# 14SD.net
KiCad netlist of a schematic drawn in Altium Designer
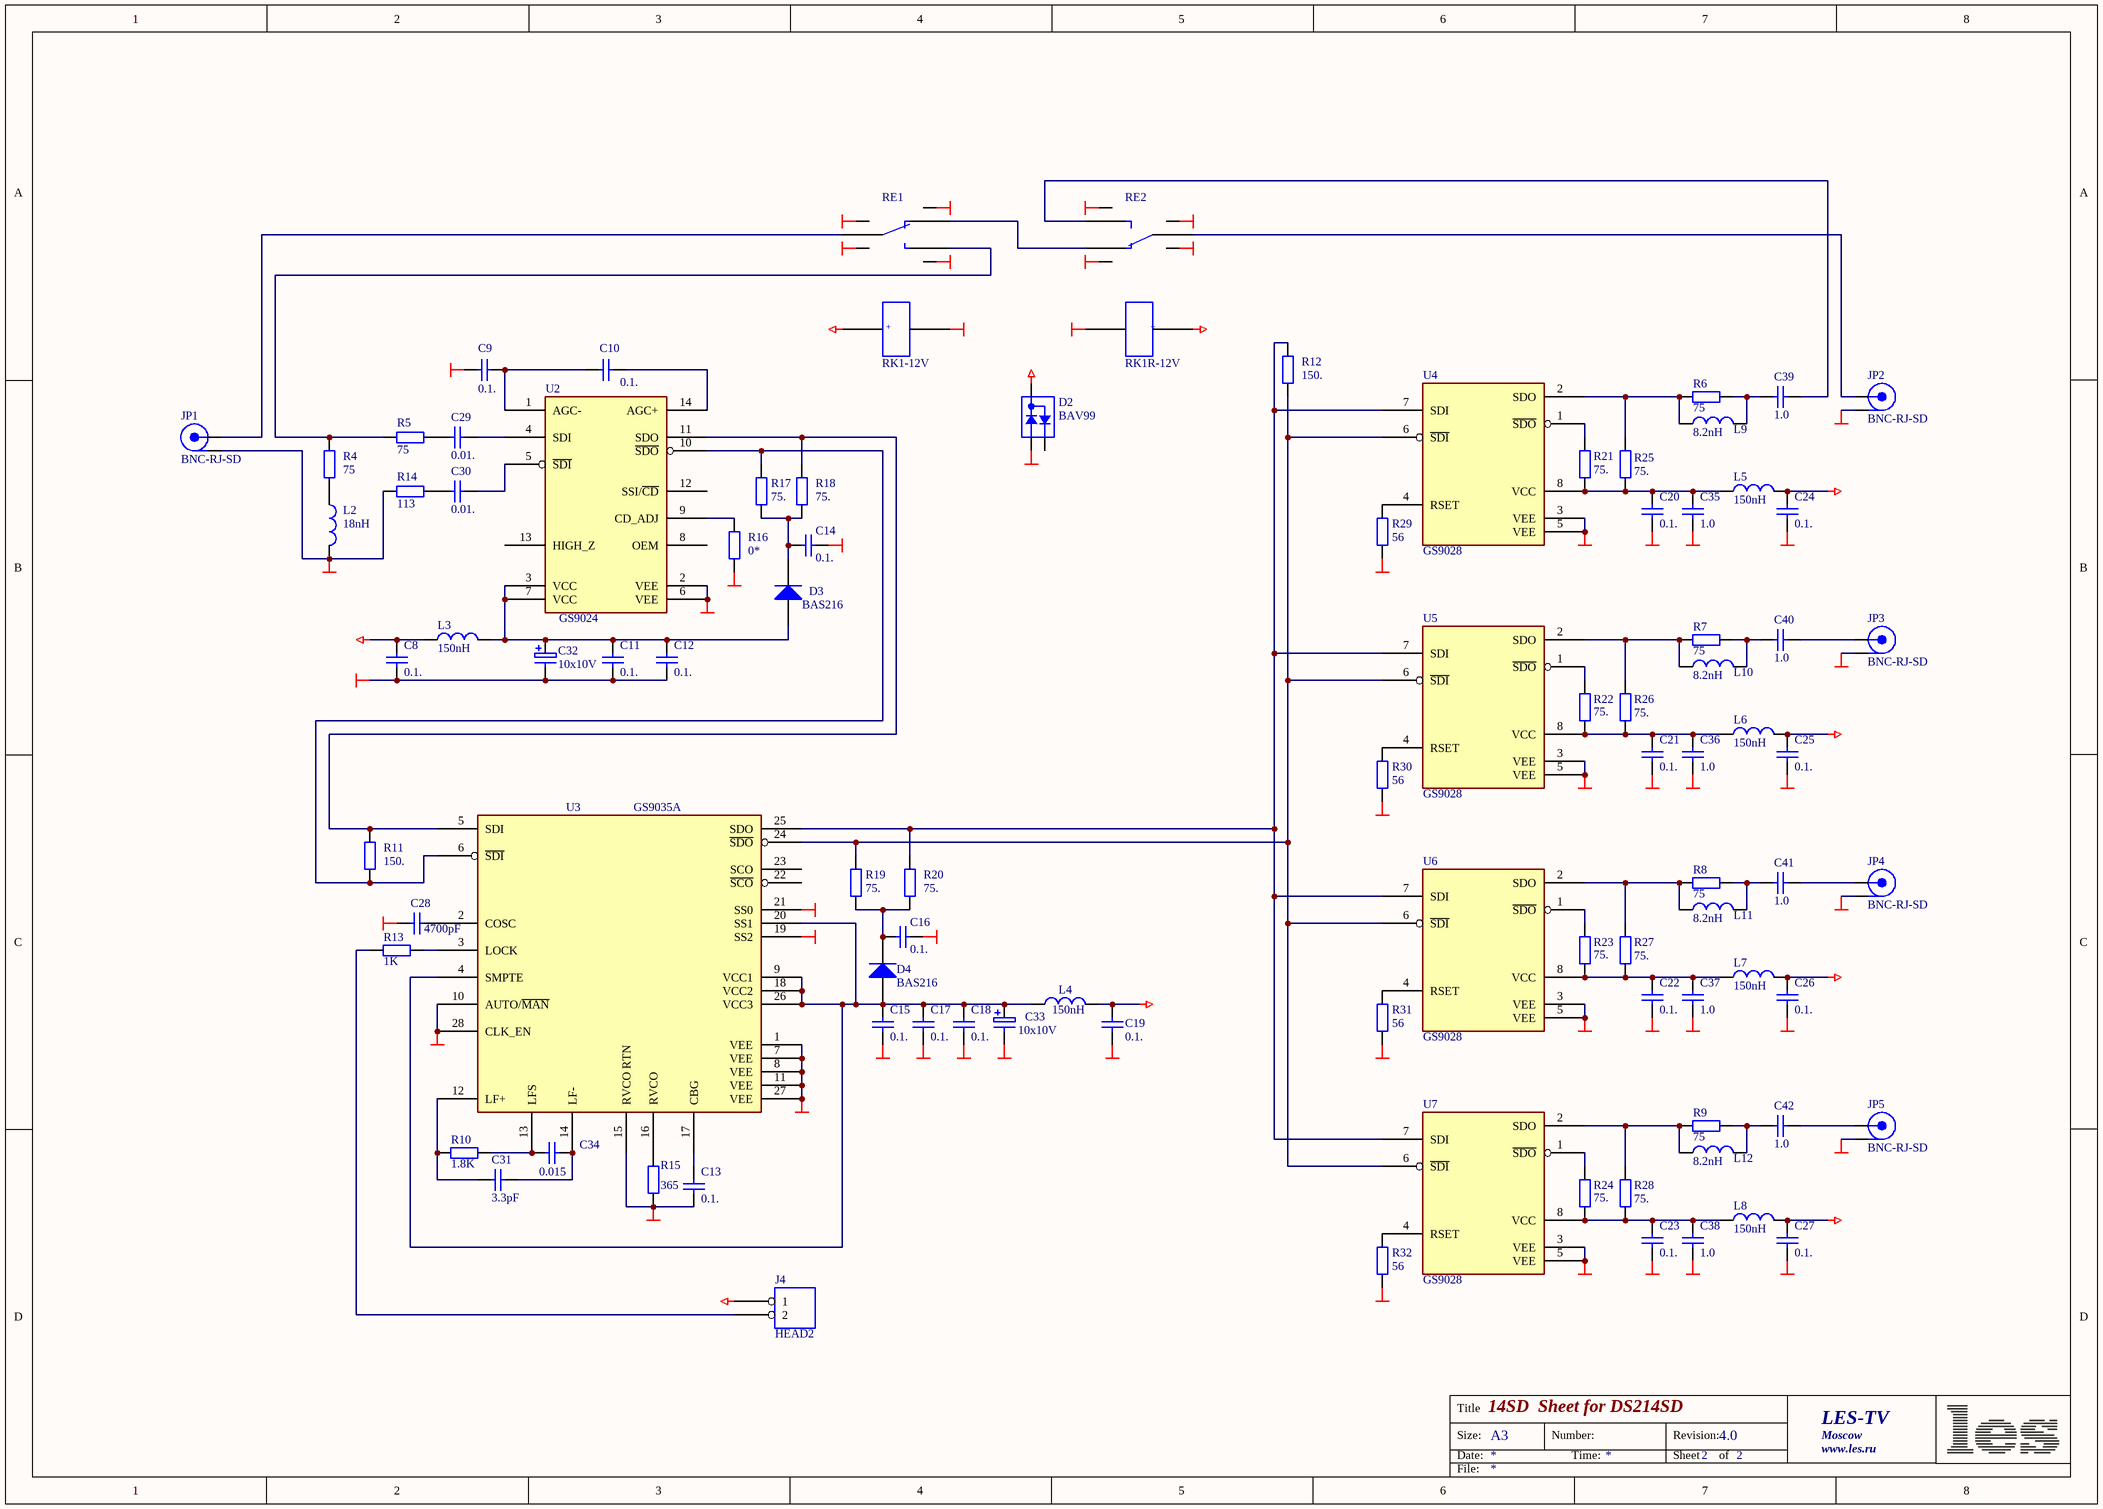
[diagram p0: 14SD.SchDoc]

(export (version "E")
  (design (tool "Eeschema 10.0.6"))
  (components
    (comp (ref "C8")
      (value "0.1.")
      (footprint "C0402")
      (description "Capacitor")
      (fields (field (name "MANUFACTURER") "Generic Components") (field (name "PUBLISHER") "Altium Limited"))
      (libsource (lib "LES") (part "Cap"))
    )
    (comp (ref "C9")
      (value "0.1.")
      (footprint "C0402")
      (description "Capacitor")
      (fields (field (name "MANUFACTURER") "Generic Components") (field (name "PUBLISHER") "Altium Limited"))
      (libsource (lib "LES") (part "Cap"))
    )
    (comp (ref "C10")
      (value "0.1.")
      (footprint "C0402")
      (description "Capacitor")
      (fields (field (name "MANUFACTURER") "Generic Components") (field (name "PUBLISHER") "Altium Limited"))
      (libsource (lib "LES") (part "Cap"))
    )
    (comp (ref "C11")
      (value "0.1.")
      (footprint "C0402")
      (description "Capacitor")
      (fields (field (name "MANUFACTURER") "Generic Components") (field (name "PUBLISHER") "Altium Limited"))
      (libsource (lib "LES") (part "Cap"))
    )
    (comp (ref "C12")
      (value "0.1.")
      (footprint "C0402")
      (description "Capacitor")
      (fields (field (name "MANUFACTURER") "Generic Components") (field (name "PUBLISHER") "Altium Limited"))
      (libsource (lib "LES") (part "Cap"))
    )
    (comp (ref "C13")
      (value "0.1.")
      (footprint "C0402")
      (description "Capacitor")
      (fields (field (name "MANUFACTURER") "Generic Components") (field (name "PUBLISHER") "Altium Limited"))
      (libsource (lib "LES") (part "Cap"))
    )
    (comp (ref "C14")
      (value "0.1.")
      (footprint "C0402")
      (description "Capacitor")
      (fields (field (name "MANUFACTURER") "Generic Components") (field (name "PUBLISHER") "Altium Limited"))
      (libsource (lib "LES") (part "Cap"))
    )
    (comp (ref "C15")
      (value "0.1.")
      (footprint "C0402")
      (description "Capacitor")
      (fields (field (name "MANUFACTURER") "Generic Components") (field (name "PUBLISHER") "Altium Limited"))
      (libsource (lib "LES") (part "Cap"))
    )
    (comp (ref "C16")
      (value "0.1.")
      (footprint "C0402")
      (description "Capacitor")
      (fields (field (name "MANUFACTURER") "Generic Components") (field (name "PUBLISHER") "Altium Limited"))
      (libsource (lib "LES") (part "Cap"))
    )
    (comp (ref "C17")
      (value "0.1.")
      (footprint "C0402")
      (description "Capacitor")
      (fields (field (name "MANUFACTURER") "Generic Components") (field (name "PUBLISHER") "Altium Limited"))
      (libsource (lib "LES") (part "Cap"))
    )
    (comp (ref "C18")
      (value "0.1.")
      (footprint "C0402")
      (description "Capacitor")
      (fields (field (name "MANUFACTURER") "Generic Components") (field (name "PUBLISHER") "Altium Limited"))
      (libsource (lib "LES") (part "Cap"))
    )
    (comp (ref "C19")
      (value "0.1.")
      (footprint "C0402")
      (description "Capacitor")
      (fields (field (name "MANUFACTURER") "Generic Components") (field (name "PUBLISHER") "Altium Limited"))
      (libsource (lib "LES") (part "Cap"))
    )
    (comp (ref "C20")
      (value "0.1.")
      (footprint "C0402")
      (description "Capacitor")
      (fields (field (name "MANUFACTURER") "Generic Components") (field (name "PUBLISHER") "Altium Limited"))
      (libsource (lib "LES") (part "Cap"))
    )
    (comp (ref "C21")
      (value "0.1.")
      (footprint "C0402")
      (description "Capacitor")
      (fields (field (name "MANUFACTURER") "Generic Components") (field (name "PUBLISHER") "Altium Limited"))
      (libsource (lib "LES") (part "Cap"))
    )
    (comp (ref "C22")
      (value "0.1.")
      (footprint "C0402")
      (description "Capacitor")
      (fields (field (name "MANUFACTURER") "Generic Components") (field (name "PUBLISHER") "Altium Limited"))
      (libsource (lib "LES") (part "Cap"))
    )
    (comp (ref "C23")
      (value "0.1.")
      (footprint "C0402")
      (description "Capacitor")
      (fields (field (name "MANUFACTURER") "Generic Components") (field (name "PUBLISHER") "Altium Limited"))
      (libsource (lib "LES") (part "Cap"))
    )
    (comp (ref "C24")
      (value "0.1.")
      (footprint "C0402")
      (description "Capacitor")
      (fields (field (name "MANUFACTURER") "Generic Components") (field (name "PUBLISHER") "Altium Limited"))
      (libsource (lib "LES") (part "Cap"))
    )
    (comp (ref "C25")
      (value "0.1.")
      (footprint "C0402")
      (description "Capacitor")
      (fields (field (name "MANUFACTURER") "Generic Components") (field (name "PUBLISHER") "Altium Limited"))
      (libsource (lib "LES") (part "Cap"))
    )
    (comp (ref "C26")
      (value "0.1.")
      (footprint "C0402")
      (description "Capacitor")
      (fields (field (name "MANUFACTURER") "Generic Components") (field (name "PUBLISHER") "Altium Limited"))
      (libsource (lib "LES") (part "Cap"))
    )
    (comp (ref "C27")
      (value "0.1.")
      (footprint "C0402")
      (description "Capacitor")
      (fields (field (name "MANUFACTURER") "Generic Components") (field (name "PUBLISHER") "Altium Limited"))
      (libsource (lib "LES") (part "Cap"))
    )
    (comp (ref "C28")
      (value "4700pF")
      (footprint "C0805")
      (description "Capacitor")
      (fields (field (name "MANUFACTURER") "Generic Components") (field (name "PUBLISHER") "Altium Limited"))
      (libsource (lib "LES") (part "Cap"))
    )
    (comp (ref "C29")
      (value "0.01.")
      (footprint "C0402")
      (description "Capacitor")
      (fields (field (name "MANUFACTURER") "Generic Components") (field (name "PUBLISHER") "Altium Limited"))
      (libsource (lib "LES") (part "Cap"))
    )
    (comp (ref "C30")
      (value "0.01.")
      (footprint "C0402")
      (description "Capacitor")
      (fields (field (name "MANUFACTURER") "Generic Components") (field (name "PUBLISHER") "Altium Limited"))
      (libsource (lib "LES") (part "Cap"))
    )
    (comp (ref "C31")
      (value "3.3pF")
      (footprint "C0805")
      (description "Capacitor")
      (fields (field (name "MANUFACTURER") "Generic Components") (field (name "PUBLISHER") "Altium Limited"))
      (libsource (lib "LES") (part "Cap"))
    )
    (comp (ref "C32")
      (value "10x10V")
      (footprint "TA1206")
      (description "Polarized Capacitor (Radial)")
      (fields (field (name "MANUFACTURER") "Generic Components") (field (name "PUBLISHER") "Altium Limited"))
      (libsource (lib "LES") (part "Cap Pol"))
    )
    (comp (ref "C33")
      (value "10x10V")
      (footprint "TA1206")
      (description "Polarized Capacitor (Radial)")
      (fields (field (name "MANUFACTURER") "Generic Components") (field (name "PUBLISHER") "Altium Limited"))
      (libsource (lib "LES") (part "Cap Pol"))
    )
    (comp (ref "C34")
      (value "0.015")
      (footprint "C0805")
      (description "Capacitor")
      (fields (field (name "MANUFACTURER") "Generic Components") (field (name "PUBLISHER") "Altium Limited"))
      (libsource (lib "LES") (part "Cap"))
    )
    (comp (ref "C35")
      (value "1.0")
      (footprint "C0805")
      (description "Capacitor")
      (fields (field (name "MANUFACTURER") "Generic Components") (field (name "PUBLISHER") "Altium Limited"))
      (libsource (lib "LES") (part "Cap"))
    )
    (comp (ref "C36")
      (value "1.0")
      (footprint "C0805")
      (description "Capacitor")
      (fields (field (name "MANUFACTURER") "Generic Components") (field (name "PUBLISHER") "Altium Limited"))
      (libsource (lib "LES") (part "Cap"))
    )
    (comp (ref "C37")
      (value "1.0")
      (footprint "C0805")
      (description "Capacitor")
      (fields (field (name "MANUFACTURER") "Generic Components") (field (name "PUBLISHER") "Altium Limited"))
      (libsource (lib "LES") (part "Cap"))
    )
    (comp (ref "C38")
      (value "1.0")
      (footprint "C0805")
      (description "Capacitor")
      (fields (field (name "MANUFACTURER") "Generic Components") (field (name "PUBLISHER") "Altium Limited"))
      (libsource (lib "LES") (part "Cap"))
    )
    (comp (ref "C39")
      (value "1.0")
      (footprint "C0805")
      (description "Capacitor")
      (fields (field (name "MANUFACTURER") "Generic Components") (field (name "PUBLISHER") "Altium Limited"))
      (libsource (lib "LES") (part "Cap"))
    )
    (comp (ref "C40")
      (value "1.0")
      (footprint "C0805")
      (description "Capacitor")
      (fields (field (name "MANUFACTURER") "Generic Components") (field (name "PUBLISHER") "Altium Limited"))
      (libsource (lib "LES") (part "Cap"))
    )
    (comp (ref "C41")
      (value "1.0")
      (footprint "C0805")
      (description "Capacitor")
      (fields (field (name "MANUFACTURER") "Generic Components") (field (name "PUBLISHER") "Altium Limited"))
      (libsource (lib "LES") (part "Cap"))
    )
    (comp (ref "C42")
      (value "1.0")
      (footprint "C0805")
      (description "Capacitor")
      (fields (field (name "MANUFACTURER") "Generic Components") (field (name "PUBLISHER") "Altium Limited"))
      (libsource (lib "LES") (part "Cap"))
    )
    (comp (ref "D2") (value "BAV99") (footprint "SOT23-BAV99") (libsource (lib "LES") (part "BAV99")))
    (comp (ref "D3")
      (value "BAS216")
      (footprint "D0805")
      (description "Default Diode")
      (fields (field (name "MANUFACTURER") "Generic Components") (field (name "PUBLISHER") "Altium Limited"))
      (libsource (lib "LES") (part "Diode"))
    )
    (comp (ref "D4")
      (value "BAS216")
      (footprint "D0805")
      (description "Default Diode")
      (fields (field (name "MANUFACTURER") "Generic Components") (field (name "PUBLISHER") "Altium Limited"))
      (libsource (lib "LES") (part "Diode"))
    )
    (comp (ref "J4") (value "HEAD2") (footprint "2SIP100") (libsource (lib "LES") (part "HEAD2")))
    (comp (ref "JP1") (value "BNC-RJ-SD") (footprint "BNC_RJ") (libsource (lib "LES") (part "BNC")))
    (comp (ref "JP2") (value "BNC-RJ-SD") (footprint "BNC_RJ") (libsource (lib "LES") (part "BNC")))
    (comp (ref "JP3") (value "BNC-RJ-SD") (footprint "BNC_RJ") (libsource (lib "LES") (part "BNC")))
    (comp (ref "JP4") (value "BNC-RJ-SD") (footprint "BNC_RJ") (libsource (lib "LES") (part "BNC")))
    (comp (ref "JP5") (value "BNC-RJ-SD") (footprint "BNC_RJ") (libsource (lib "LES") (part "BNC")))
    (comp (ref "L2") (value "18nH") (footprint "LES:L0805") (libsource (lib "LES") (part "INDUCTOR")))
    (comp (ref "L3") (value "150nH") (footprint "LES:L0805") (libsource (lib "LES") (part "INDUCTOR")))
    (comp (ref "L4") (value "150nH") (footprint "LES:L0805") (libsource (lib "LES") (part "INDUCTOR")))
    (comp (ref "L5") (value "150nH") (footprint "LES:L0805") (libsource (lib "") (part "INDUCTOR_1")))
    (comp (ref "L6") (value "150nH") (footprint "LES:L0805") (libsource (lib "") (part "INDUCTOR_1")))
    (comp (ref "L7") (value "150nH") (footprint "LES:L0805") (libsource (lib "") (part "INDUCTOR_1")))
    (comp (ref "L8") (value "150nH") (footprint "LES:L0805") (libsource (lib "") (part "INDUCTOR_1")))
    (comp (ref "L9") (value "8.2nH") (footprint "LES:L0805") (libsource (lib "LES") (part "INDUCTOR")))
    (comp (ref "L10") (value "8.2nH") (footprint "LES:L0805") (libsource (lib "LES") (part "INDUCTOR")))
    (comp (ref "L11") (value "8.2nH") (footprint "LES:L0805") (libsource (lib "LES") (part "INDUCTOR")))
    (comp (ref "L12") (value "8.2nH") (footprint "LES:L0805") (libsource (lib "LES") (part "INDUCTOR")))
    (comp (ref "R4")
      (value "75")
      (footprint "R0805")
      (description "Resistor")
      (fields (field (name "MANUFACTURER") "Generic Components") (field (name "PUBLISHER") "Altium Limited"))
      (libsource (lib "LES") (part "Res"))
    )
    (comp (ref "R5")
      (value "75")
      (footprint "R0805")
      (description "Resistor")
      (fields (field (name "MANUFACTURER") "Generic Components") (field (name "PUBLISHER") "Altium Limited"))
      (libsource (lib "") (part "Res_2"))
    )
    (comp (ref "R6")
      (value "75")
      (footprint "R0805")
      (description "Resistor")
      (fields (field (name "MANUFACTURER") "Generic Components") (field (name "PUBLISHER") "Altium Limited"))
      (libsource (lib "") (part "Res_3"))
    )
    (comp (ref "R7")
      (value "75")
      (footprint "R0805")
      (description "Resistor")
      (fields (field (name "MANUFACTURER") "Generic Components") (field (name "PUBLISHER") "Altium Limited"))
      (libsource (lib "") (part "Res_3"))
    )
    (comp (ref "R8")
      (value "75")
      (footprint "R0805")
      (description "Resistor")
      (fields (field (name "MANUFACTURER") "Generic Components") (field (name "PUBLISHER") "Altium Limited"))
      (libsource (lib "") (part "Res_3"))
    )
    (comp (ref "R9")
      (value "75")
      (footprint "R0805")
      (description "Resistor")
      (fields (field (name "MANUFACTURER") "Generic Components") (field (name "PUBLISHER") "Altium Limited"))
      (libsource (lib "") (part "Res_3"))
    )
    (comp (ref "R10")
      (value "1.8K")
      (footprint "R0805")
      (description "Resistor")
      (fields (field (name "MANUFACTURER") "Generic Components") (field (name "PUBLISHER") "Altium Limited"))
      (libsource (lib "") (part "Res_2"))
    )
    (comp (ref "R11")
      (value "150.")
      (footprint "R0402")
      (description "Resistor")
      (fields (field (name "MANUFACTURER") "Generic Components") (field (name "PUBLISHER") "Altium Limited"))
      (libsource (lib "LES") (part "Res"))
    )
    (comp (ref "R12")
      (value "150.")
      (footprint "R0402")
      (description "Resistor")
      (fields (field (name "MANUFACTURER") "Generic Components") (field (name "PUBLISHER") "Altium Limited"))
      (libsource (lib "LES") (part "Res"))
    )
    (comp (ref "R13")
      (value "1K")
      (footprint "R0805")
      (description "Resistor")
      (fields (field (name "MANUFACTURER") "Generic Components") (field (name "PUBLISHER") "Altium Limited"))
      (libsource (lib "") (part "Res_2"))
    )
    (comp (ref "R14")
      (value "113")
      (footprint "R0805")
      (description "Resistor")
      (fields (field (name "MANUFACTURER") "Generic Components") (field (name "PUBLISHER") "Altium Limited"))
      (libsource (lib "") (part "Res_2"))
    )
    (comp (ref "R15")
      (value "365")
      (footprint "R0805")
      (description "Resistor")
      (fields (field (name "MANUFACTURER") "Generic Components") (field (name "PUBLISHER") "Altium Limited"))
      (libsource (lib "") (part "Res_1"))
    )
    (comp (ref "R16")
      (value "0*")
      (footprint "R0402")
      (description "Resistor")
      (fields (field (name "MANUFACTURER") "Generic Components") (field (name "PUBLISHER") "Altium Limited"))
      (libsource (lib "LES") (part "Res"))
    )
    (comp (ref "R17")
      (value "75.")
      (footprint "R0402")
      (description "Resistor")
      (fields (field (name "MANUFACTURER") "Generic Components") (field (name "PUBLISHER") "Altium Limited"))
      (libsource (lib "LES") (part "Res"))
    )
    (comp (ref "R18")
      (value "75.")
      (footprint "R0402")
      (description "Resistor")
      (fields (field (name "MANUFACTURER") "Generic Components") (field (name "PUBLISHER") "Altium Limited"))
      (libsource (lib "LES") (part "Res"))
    )
    (comp (ref "R19")
      (value "75.")
      (footprint "R0402")
      (description "Resistor")
      (fields (field (name "MANUFACTURER") "Generic Components") (field (name "PUBLISHER") "Altium Limited"))
      (libsource (lib "LES") (part "Res"))
    )
    (comp (ref "R20")
      (value "75.")
      (footprint "R0402")
      (description "Resistor")
      (fields (field (name "MANUFACTURER") "Generic Components") (field (name "PUBLISHER") "Altium Limited"))
      (libsource (lib "LES") (part "Res"))
    )
    (comp (ref "R21")
      (value "75.")
      (footprint "R0402")
      (description "Resistor")
      (fields (field (name "MANUFACTURER") "Generic Components") (field (name "PUBLISHER") "Altium Limited"))
      (libsource (lib "LES") (part "Res"))
    )
    (comp (ref "R22")
      (value "75.")
      (footprint "R0402")
      (description "Resistor")
      (fields (field (name "MANUFACTURER") "Generic Components") (field (name "PUBLISHER") "Altium Limited"))
      (libsource (lib "LES") (part "Res"))
    )
    (comp (ref "R23")
      (value "75.")
      (footprint "R0402")
      (description "Resistor")
      (fields (field (name "MANUFACTURER") "Generic Components") (field (name "PUBLISHER") "Altium Limited"))
      (libsource (lib "LES") (part "Res"))
    )
    (comp (ref "R24")
      (value "75.")
      (footprint "R0402")
      (description "Resistor")
      (fields (field (name "MANUFACTURER") "Generic Components") (field (name "PUBLISHER") "Altium Limited"))
      (libsource (lib "LES") (part "Res"))
    )
    (comp (ref "R25")
      (value "75.")
      (footprint "R0402")
      (description "Resistor")
      (fields (field (name "MANUFACTURER") "Generic Components") (field (name "PUBLISHER") "Altium Limited"))
      (libsource (lib "LES") (part "Res"))
    )
    (comp (ref "R26")
      (value "75.")
      (footprint "R0402")
      (description "Resistor")
      (fields (field (name "MANUFACTURER") "Generic Components") (field (name "PUBLISHER") "Altium Limited"))
      (libsource (lib "LES") (part "Res"))
    )
    (comp (ref "R27")
      (value "75.")
      (footprint "R0402")
      (description "Resistor")
      (fields (field (name "MANUFACTURER") "Generic Components") (field (name "PUBLISHER") "Altium Limited"))
      (libsource (lib "LES") (part "Res"))
    )
    (comp (ref "R28")
      (value "75.")
      (footprint "R0402")
      (description "Resistor")
      (fields (field (name "MANUFACTURER") "Generic Components") (field (name "PUBLISHER") "Altium Limited"))
      (libsource (lib "LES") (part "Res"))
    )
    (comp (ref "R29")
      (value "56")
      (footprint "R0805")
      (description "Resistor")
      (fields (field (name "MANUFACTURER") "Generic Components") (field (name "PUBLISHER") "Altium Limited"))
      (libsource (lib "LES") (part "Res"))
    )
    (comp (ref "R30")
      (value "56")
      (footprint "R0805")
      (description "Resistor")
      (fields (field (name "MANUFACTURER") "Generic Components") (field (name "PUBLISHER") "Altium Limited"))
      (libsource (lib "LES") (part "Res"))
    )
    (comp (ref "R31")
      (value "56")
      (footprint "R0805")
      (description "Resistor")
      (fields (field (name "MANUFACTURER") "Generic Components") (field (name "PUBLISHER") "Altium Limited"))
      (libsource (lib "LES") (part "Res"))
    )
    (comp (ref "R32")
      (value "56")
      (footprint "R0805")
      (description "Resistor")
      (fields (field (name "MANUFACTURER") "Generic Components") (field (name "PUBLISHER") "Altium Limited"))
      (libsource (lib "LES") (part "Res"))
    )
    (comp (ref "RE1") (value "RK1-12V") (footprint "RELAY RK") (libsource (lib "LES") (part "RELAY RK1")))
    (comp (ref "RE2") (value "RK1R-12V") (footprint "RELAY RK") (libsource (lib "LES") (part "RELAY RK1R")))
    (comp (ref "U2") (value "GS9024") (footprint "LES:SO-14") (libsource (lib "LES") (part "GS9024")))
    (comp (ref "U3") (value "GS9035A") (footprint "PLCC-28") (libsource (lib "LES") (part "GS9035A")))
    (comp (ref "U4") (value "GS9028") (footprint "SO-8") (libsource (lib "LES") (part "GS9028")))
    (comp (ref "U5") (value "GS9028") (footprint "SO-8") (libsource (lib "LES") (part "GS9028")))
    (comp (ref "U6") (value "GS9028") (footprint "SO-8") (libsource (lib "LES") (part "GS9028")))
    (comp (ref "U7") (value "GS9028") (footprint "SO-8") (libsource (lib "LES") (part "GS9028")))
  )
  (nets
    (net (code "1") (name "+5V") (class "Default")
      (node (ref "C19") (pin "2") (pinfunction "2_2") (pintype "passive"))
      (node (ref "C24") (pin "2") (pinfunction "2_2") (pintype "passive"))
      (node (ref "C25") (pin "2") (pinfunction "2_2") (pintype "passive"))
      (node (ref "C26") (pin "2") (pinfunction "2_2") (pintype "passive"))
      (node (ref "C27") (pin "2") (pinfunction "2_2") (pintype "passive"))
      (node (ref "C8") (pin "2") (pinfunction "2_2") (pintype "passive"))
      (node (ref "J4") (pin "1") (pinfunction "1_1") (pintype "passive"))
      (node (ref "L3") (pin "1") (pinfunction "1_1") (pintype "passive"))
      (node (ref "L4") (pin "2") (pinfunction "2_2") (pintype "passive"))
      (node (ref "L5") (pin "1") (pinfunction "1_1") (pintype "passive"))
      (node (ref "L6") (pin "1") (pinfunction "1_1") (pintype "passive"))
      (node (ref "L7") (pin "1") (pinfunction "1_1") (pintype "passive"))
      (node (ref "L8") (pin "1") (pinfunction "1_1") (pintype "passive"))
    )
    (net (code "2") (name "GND") (class "Default")
      (node (ref "C11") (pin "1") (pinfunction "1_1") (pintype "passive"))
      (node (ref "C12") (pin "1") (pinfunction "1_1") (pintype "passive"))
      (node (ref "C13") (pin "1") (pinfunction "1_1") (pintype "passive"))
      (node (ref "C14") (pin "1") (pinfunction "1_1") (pintype "passive"))
      (node (ref "C15") (pin "1") (pinfunction "1_1") (pintype "passive"))
      (node (ref "C16") (pin "1") (pinfunction "1_1") (pintype "passive"))
      (node (ref "C17") (pin "1") (pinfunction "1_1") (pintype "passive"))
      (node (ref "C18") (pin "1") (pinfunction "1_1") (pintype "passive"))
      (node (ref "C19") (pin "1") (pinfunction "1_1") (pintype "passive"))
      (node (ref "C20") (pin "1") (pinfunction "1_1") (pintype "passive"))
      (node (ref "C21") (pin "1") (pinfunction "1_1") (pintype "passive"))
      (node (ref "C22") (pin "1") (pinfunction "1_1") (pintype "passive"))
      (node (ref "C23") (pin "1") (pinfunction "1_1") (pintype "passive"))
      (node (ref "C24") (pin "1") (pinfunction "1_1") (pintype "passive"))
      (node (ref "C25") (pin "1") (pinfunction "1_1") (pintype "passive"))
      (node (ref "C26") (pin "1") (pinfunction "1_1") (pintype "passive"))
      (node (ref "C27") (pin "1") (pinfunction "1_1") (pintype "passive"))
      (node (ref "C28") (pin "1") (pinfunction "1_1") (pintype "passive"))
      (node (ref "C32") (pin "2") (pinfunction "2_2") (pintype "passive"))
      (node (ref "C33") (pin "2") (pinfunction "2_2") (pintype "passive"))
      (node (ref "C35") (pin "1") (pinfunction "1_1") (pintype "passive"))
      (node (ref "C36") (pin "1") (pinfunction "1_1") (pintype "passive"))
      (node (ref "C37") (pin "1") (pinfunction "1_1") (pintype "passive"))
      (node (ref "C38") (pin "1") (pinfunction "1_1") (pintype "passive"))
      (node (ref "C8") (pin "1") (pinfunction "1_1") (pintype "passive"))
      (node (ref "C9") (pin "1") (pinfunction "1_1") (pintype "passive"))
      (node (ref "D2") (pin "2") (pinfunction "A_2") (pintype "passive"))
      (node (ref "JP1") (pin "2") (pinfunction "2_2") (pintype "passive"))
      (node (ref "JP2") (pin "2") (pinfunction "2_2") (pintype "passive"))
      (node (ref "JP3") (pin "2") (pinfunction "2_2") (pintype "passive"))
      (node (ref "JP4") (pin "2") (pinfunction "2_2") (pintype "passive"))
      (node (ref "JP5") (pin "2") (pinfunction "2_2") (pintype "passive"))
      (node (ref "L2") (pin "2") (pinfunction "2_2") (pintype "passive"))
      (node (ref "R14") (pin "2") (pinfunction "2_2") (pintype "passive"))
      (node (ref "R15") (pin "2") (pinfunction "2_2") (pintype "passive"))
      (node (ref "R16") (pin "1") (pinfunction "1_1") (pintype "passive"))
      (node (ref "R29") (pin "1") (pinfunction "1_1") (pintype "passive"))
      (node (ref "R30") (pin "1") (pinfunction "1_1") (pintype "passive"))
      (node (ref "R31") (pin "1") (pinfunction "1_1") (pintype "passive"))
      (node (ref "R32") (pin "1") (pinfunction "1_1") (pintype "passive"))
      (node (ref "RE1") (pin "1") (pinfunction "W-_1") (pintype "passive"))
      (node (ref "RE1") (pin "10") (pinfunction "10_10") (pintype "passive"))
      (node (ref "RE1") (pin "12") (pinfunction "12_12") (pintype "passive"))
      (node (ref "RE1") (pin "13") (pinfunction "13_13") (pintype "passive"))
      (node (ref "RE1") (pin "9") (pinfunction "9_9") (pintype "passive"))
      (node (ref "RE2") (pin "1") (pinfunction "W-_1") (pintype "passive"))
      (node (ref "RE2") (pin "10") (pinfunction "10_10") (pintype "passive"))
      (node (ref "RE2") (pin "12") (pinfunction "12_12") (pintype "passive"))
      (node (ref "RE2") (pin "13") (pinfunction "13_13") (pintype "passive"))
      (node (ref "RE2") (pin "9") (pinfunction "9_9") (pintype "passive"))
      (node (ref "U2") (pin "2") (pinfunction "VEE_2") (pintype "power_in"))
      (node (ref "U2") (pin "6") (pinfunction "VEE_6") (pintype "power_in"))
      (node (ref "U3") (pin "1") (pinfunction "VEE_1") (pintype "power_in"))
      (node (ref "U3") (pin "10") (pinfunction "AUTO/~{MAN}_10") (pintype "passive"))
      (node (ref "U3") (pin "11") (pinfunction "VEE_11") (pintype "power_in"))
      (node (ref "U3") (pin "15") (pinfunction "RVCO_RTN_15") (pintype "passive"))
      (node (ref "U3") (pin "19") (pinfunction "SS2_19") (pintype "passive"))
      (node (ref "U3") (pin "21") (pinfunction "SS0_21") (pintype "passive"))
      (node (ref "U3") (pin "27") (pinfunction "VEE_27") (pintype "power_in"))
      (node (ref "U3") (pin "28") (pinfunction "CLK_EN_28") (pintype "passive"))
      (node (ref "U3") (pin "7") (pinfunction "VEE_7") (pintype "power_in"))
      (node (ref "U3") (pin "8") (pinfunction "VEE_8") (pintype "power_in"))
      (node (ref "U4") (pin "3") (pinfunction "VEE_3") (pintype "power_in"))
      (node (ref "U4") (pin "5") (pinfunction "VEE_5") (pintype "power_in"))
      (node (ref "U5") (pin "3") (pinfunction "VEE_3") (pintype "power_in"))
      (node (ref "U5") (pin "5") (pinfunction "VEE_5") (pintype "power_in"))
      (node (ref "U6") (pin "3") (pinfunction "VEE_3") (pintype "power_in"))
      (node (ref "U6") (pin "5") (pinfunction "VEE_5") (pintype "power_in"))
      (node (ref "U7") (pin "3") (pinfunction "VEE_3") (pintype "power_in"))
      (node (ref "U7") (pin "5") (pinfunction "VEE_5") (pintype "power_in"))
    )
    (net (code "3") (name "Net-(C29-Pad1)") (class "Default")
      (node (ref "C29") (pin "1") (pinfunction "1_1") (pintype "passive"))
      (node (ref "R5") (pin "1") (pinfunction "1_1") (pintype "passive"))
    )
    (net (code "4") (name "Net-(C30-Pad1)") (class "Default")
      (node (ref "C30") (pin "1") (pinfunction "1_1") (pintype "passive"))
      (node (ref "R14") (pin "1") (pinfunction "1_1") (pintype "passive"))
    )
    (net (code "5") (name "Net-(C39-Pad2)") (class "Default")
      (node (ref "C39") (pin "2") (pinfunction "2_2") (pintype "passive"))
      (node (ref "L9") (pin "2") (pinfunction "2_2") (pintype "passive"))
      (node (ref "R6") (pin "2") (pinfunction "2_2") (pintype "passive"))
    )
    (net (code "6") (name "Net-(C40-Pad1)") (class "Default")
      (node (ref "C40") (pin "1") (pinfunction "1_1") (pintype "passive"))
      (node (ref "JP3") (pin "1") (pinfunction "1_1") (pintype "passive"))
    )
    (net (code "7") (name "Net-(C40-Pad2)") (class "Default")
      (node (ref "C40") (pin "2") (pinfunction "2_2") (pintype "passive"))
      (node (ref "L10") (pin "2") (pinfunction "2_2") (pintype "passive"))
      (node (ref "R7") (pin "2") (pinfunction "2_2") (pintype "passive"))
    )
    (net (code "8") (name "Net-(C41-Pad1)") (class "Default")
      (node (ref "C41") (pin "1") (pinfunction "1_1") (pintype "passive"))
      (node (ref "JP4") (pin "1") (pinfunction "1_1") (pintype "passive"))
    )
    (net (code "9") (name "Net-(C41-Pad2)") (class "Default")
      (node (ref "C41") (pin "2") (pinfunction "2_2") (pintype "passive"))
      (node (ref "L11") (pin "2") (pinfunction "2_2") (pintype "passive"))
      (node (ref "R8") (pin "2") (pinfunction "2_2") (pintype "passive"))
    )
    (net (code "10") (name "Net-(C42-Pad1)") (class "Default")
      (node (ref "C42") (pin "1") (pinfunction "1_1") (pintype "passive"))
      (node (ref "JP5") (pin "1") (pinfunction "1_1") (pintype "passive"))
    )
    (net (code "11") (name "Net-(C42-Pad2)") (class "Default")
      (node (ref "C42") (pin "2") (pinfunction "2_2") (pintype "passive"))
      (node (ref "L12") (pin "2") (pinfunction "2_2") (pintype "passive"))
      (node (ref "R9") (pin "2") (pinfunction "2_2") (pintype "passive"))
    )
    (net (code "12") (name "Net-(D3-A)") (class "Default")
      (node (ref "C11") (pin "2") (pinfunction "2_2") (pintype "passive"))
      (node (ref "C12") (pin "2") (pinfunction "2_2") (pintype "passive"))
      (node (ref "C32") (pin "1") (pinfunction "1_1") (pintype "passive"))
      (node (ref "D3") (pin "1") (pinfunction "A_1") (pintype "passive"))
      (node (ref "L3") (pin "2") (pinfunction "2_2") (pintype "passive"))
      (node (ref "U2") (pin "3") (pinfunction "VCC_3") (pintype "power_in"))
      (node (ref "U2") (pin "7") (pinfunction "VCC_7") (pintype "power_in"))
    )
    (net (code "13") (name "Net-(D3-K)") (class "Default")
      (node (ref "C14") (pin "2") (pinfunction "2_2") (pintype "passive"))
      (node (ref "D3") (pin "2") (pinfunction "K_2") (pintype "passive"))
      (node (ref "R17") (pin "1") (pinfunction "1_1") (pintype "passive"))
      (node (ref "R18") (pin "1") (pinfunction "1_1") (pintype "passive"))
    )
    (net (code "14") (name "Net-(D4-A)") (class "Default")
      (node (ref "C15") (pin "2") (pinfunction "2_2") (pintype "passive"))
      (node (ref "C17") (pin "2") (pinfunction "2_2") (pintype "passive"))
      (node (ref "C18") (pin "2") (pinfunction "2_2") (pintype "passive"))
      (node (ref "C33") (pin "1") (pinfunction "1_1") (pintype "passive"))
      (node (ref "D4") (pin "1") (pinfunction "A_1") (pintype "passive"))
      (node (ref "L4") (pin "1") (pinfunction "1_1") (pintype "passive"))
      (node (ref "U3") (pin "18") (pinfunction "VCC2_18") (pintype "power_in"))
      (node (ref "U3") (pin "20") (pinfunction "SS1_20") (pintype "passive"))
      (node (ref "U3") (pin "26") (pinfunction "VCC3_26") (pintype "power_in"))
      (node (ref "U3") (pin "4") (pinfunction "SMPTE_4") (pintype "passive"))
      (node (ref "U3") (pin "9") (pinfunction "VCC1_9") (pintype "power_in"))
    )
    (net (code "15") (name "Net-(D4-K)") (class "Default")
      (node (ref "C16") (pin "2") (pinfunction "2_2") (pintype "passive"))
      (node (ref "D4") (pin "2") (pinfunction "K_2") (pintype "passive"))
      (node (ref "R19") (pin "1") (pinfunction "1_1") (pintype "passive"))
      (node (ref "R20") (pin "1") (pinfunction "1_1") (pintype "passive"))
    )
    (net (code "16") (name "Net-(J4-Pad2)") (class "Default")
      (node (ref "J4") (pin "2") (pinfunction "2_2") (pintype "passive"))
      (node (ref "R13") (pin "2") (pinfunction "2_2") (pintype "passive"))
    )
    (net (code "17") (name "Net-(L2-Pad1)") (class "Default")
      (node (ref "L2") (pin "1") (pinfunction "1_1") (pintype "passive"))
      (node (ref "R4") (pin "1") (pinfunction "1_1") (pintype "passive"))
    )
    (net (code "18") (name "Net-(RE1-COM)") (class "Default")
      (node (ref "JP1") (pin "1") (pinfunction "1_1") (pintype "passive"))
      (node (ref "RE1") (pin "11") (pinfunction "COM_11") (pintype "passive"))
    )
    (net (code "19") (name "Net-(RE1-NC)") (class "Default")
      (node (ref "RE1") (pin "14") (pinfunction "NC_14") (pintype "passive"))
      (node (ref "RE2") (pin "8") (pinfunction "NC_8") (pintype "passive"))
    )
    (net (code "20") (name "Net-(RE1-NO)") (class "Default")
      (node (ref "R4") (pin "2") (pinfunction "2_2") (pintype "passive"))
      (node (ref "R5") (pin "2") (pinfunction "2_2") (pintype "passive"))
      (node (ref "RE1") (pin "8") (pinfunction "NO_8") (pintype "passive"))
    )
    (net (code "21") (name "Net-(RE2-COM)") (class "Default")
      (node (ref "JP2") (pin "1") (pinfunction "1_1") (pintype "passive"))
      (node (ref "RE2") (pin "11") (pinfunction "COM_11") (pintype "passive"))
    )
    (net (code "22") (name "Net-(RE2-NO)") (class "Default")
      (node (ref "C39") (pin "1") (pinfunction "1_1") (pintype "passive"))
      (node (ref "RE2") (pin "14") (pinfunction "NO_14") (pintype "passive"))
    )
    (net (code "23") (name "Net-(U2-AGC+)") (class "Default")
      (node (ref "C10") (pin "2") (pinfunction "2_2") (pintype "passive"))
      (node (ref "U2") (pin "14") (pinfunction "AGC+_14") (pintype "passive"))
    )
    (net (code "24") (name "Net-(U2-AGC-)") (class "Default")
      (node (ref "C10") (pin "1") (pinfunction "1_1") (pintype "passive"))
      (node (ref "C9") (pin "2") (pinfunction "2_2") (pintype "passive"))
      (node (ref "U2") (pin "1") (pinfunction "AGC-_1") (pintype "passive"))
    )
    (net (code "25") (name "Net-(U2-CD_ADJ)") (class "Default")
      (node (ref "R16") (pin "2") (pinfunction "2_2") (pintype "passive"))
      (node (ref "U2") (pin "9") (pinfunction "CD_ADJ_9") (pintype "passive"))
    )
    (net (code "26") (name "Net-(U2-SDI)") (class "Default")
      (node (ref "C29") (pin "2") (pinfunction "2_2") (pintype "passive"))
      (node (ref "U2") (pin "4") (pinfunction "SDI_4") (pintype "passive"))
    )
    (net (code "27") (name "Net-(U2-SDO)") (class "Default")
      (node (ref "R11") (pin "2") (pinfunction "2_2") (pintype "passive"))
      (node (ref "R18") (pin "2") (pinfunction "2_2") (pintype "passive"))
      (node (ref "U2") (pin "11") (pinfunction "SDO_11") (pintype "passive"))
      (node (ref "U3") (pin "5") (pinfunction "SDI_5") (pintype "passive"))
    )
    (net (code "28") (name "Net-(U2-~{SDI})") (class "Default")
      (node (ref "C30") (pin "2") (pinfunction "2_2") (pintype "passive"))
      (node (ref "U2") (pin "5") (pinfunction "~{SDI}_5") (pintype "passive"))
    )
    (net (code "29") (name "Net-(U2-~{SDO})") (class "Default")
      (node (ref "R11") (pin "1") (pinfunction "1_1") (pintype "passive"))
      (node (ref "R17") (pin "2") (pinfunction "2_2") (pintype "passive"))
      (node (ref "U2") (pin "10") (pinfunction "~{SDO}_10") (pintype "passive"))
      (node (ref "U3") (pin "6") (pinfunction "~{SDI}_6") (pintype "passive"))
    )
    (net (code "30") (name "Net-(U3-CBG)") (class "Default")
      (node (ref "C13") (pin "2") (pinfunction "2_2") (pintype "passive"))
      (node (ref "U3") (pin "17") (pinfunction "CBG_17") (pintype "passive"))
    )
    (net (code "31") (name "Net-(U3-COSC)") (class "Default")
      (node (ref "C28") (pin "2") (pinfunction "2_2") (pintype "passive"))
      (node (ref "U3") (pin "2") (pinfunction "COSC_2") (pintype "passive"))
    )
    (net (code "32") (name "Net-(U3-LF+)") (class "Default")
      (node (ref "C31") (pin "1") (pinfunction "1_1") (pintype "passive"))
      (node (ref "R10") (pin "2") (pinfunction "2_2") (pintype "passive"))
      (node (ref "U3") (pin "12") (pinfunction "LF+_12") (pintype "passive"))
    )
    (net (code "33") (name "Net-(U3-LF-)") (class "Default")
      (node (ref "C31") (pin "2") (pinfunction "2_2") (pintype "passive"))
      (node (ref "C34") (pin "2") (pinfunction "2_2") (pintype "passive"))
      (node (ref "U3") (pin "14") (pinfunction "LF-_14") (pintype "passive"))
    )
    (net (code "34") (name "Net-(U3-LFS)") (class "Default")
      (node (ref "C34") (pin "1") (pinfunction "1_1") (pintype "passive"))
      (node (ref "R10") (pin "1") (pinfunction "1_1") (pintype "passive"))
      (node (ref "U3") (pin "13") (pinfunction "LFS_13") (pintype "passive"))
    )
    (net (code "35") (name "Net-(U3-LOCK)") (class "Default")
      (node (ref "R13") (pin "1") (pinfunction "1_1") (pintype "passive"))
      (node (ref "U3") (pin "3") (pinfunction "LOCK_3") (pintype "passive"))
    )
    (net (code "36") (name "Net-(U3-RVCO)") (class "Default")
      (node (ref "R15") (pin "1") (pinfunction "1_1") (pintype "passive"))
      (node (ref "U3") (pin "16") (pinfunction "RVCO_16") (pintype "passive"))
    )
    (net (code "37") (name "Net-(U3-SDO)") (class "Default")
      (node (ref "R12") (pin "2") (pinfunction "2_2") (pintype "passive"))
      (node (ref "R20") (pin "2") (pinfunction "2_2") (pintype "passive"))
      (node (ref "U3") (pin "25") (pinfunction "SDO_25") (pintype "passive"))
      (node (ref "U4") (pin "7") (pinfunction "SDI_7") (pintype "passive"))
      (node (ref "U5") (pin "7") (pinfunction "SDI_7") (pintype "passive"))
      (node (ref "U6") (pin "7") (pinfunction "SDI_7") (pintype "passive"))
      (node (ref "U7") (pin "7") (pinfunction "SDI_7") (pintype "passive"))
    )
    (net (code "38") (name "Net-(U3-~{SDO})") (class "Default")
      (node (ref "R12") (pin "1") (pinfunction "1_1") (pintype "passive"))
      (node (ref "R19") (pin "2") (pinfunction "2_2") (pintype "passive"))
      (node (ref "U3") (pin "24") (pinfunction "~{SDO}_24") (pintype "passive"))
      (node (ref "U4") (pin "6") (pinfunction "~{SDI}_6") (pintype "passive"))
      (node (ref "U5") (pin "6") (pinfunction "~{SDI}_6") (pintype "passive"))
      (node (ref "U6") (pin "6") (pinfunction "~{SDI}_6") (pintype "passive"))
      (node (ref "U7") (pin "6") (pinfunction "~{SDI}_6") (pintype "passive"))
    )
    (net (code "39") (name "Net-(U4-RSET)") (class "Default")
      (node (ref "R29") (pin "2") (pinfunction "2_2") (pintype "passive"))
      (node (ref "U4") (pin "4") (pinfunction "RSET_4") (pintype "passive"))
    )
    (net (code "40") (name "Net-(U4-SDO)") (class "Default")
      (node (ref "L9") (pin "1") (pinfunction "1_1") (pintype "passive"))
      (node (ref "R25") (pin "2") (pinfunction "2_2") (pintype "passive"))
      (node (ref "R6") (pin "1") (pinfunction "1_1") (pintype "passive"))
      (node (ref "U4") (pin "2") (pinfunction "SDO_2") (pintype "passive"))
    )
    (net (code "41") (name "Net-(U4-VCC)") (class "Default")
      (node (ref "C20") (pin "2") (pinfunction "2_2") (pintype "passive"))
      (node (ref "C35") (pin "2") (pinfunction "2_2") (pintype "passive"))
      (node (ref "L5") (pin "2") (pinfunction "2_2") (pintype "passive"))
      (node (ref "R21") (pin "1") (pinfunction "1_1") (pintype "passive"))
      (node (ref "R25") (pin "1") (pinfunction "1_1") (pintype "passive"))
      (node (ref "U4") (pin "8") (pinfunction "VCC_8") (pintype "power_in"))
    )
    (net (code "42") (name "Net-(U4-~{SDO})") (class "Default")
      (node (ref "R21") (pin "2") (pinfunction "2_2") (pintype "passive"))
      (node (ref "U4") (pin "1") (pinfunction "~{SDO}_1") (pintype "passive"))
    )
    (net (code "43") (name "Net-(U5-RSET)") (class "Default")
      (node (ref "R30") (pin "2") (pinfunction "2_2") (pintype "passive"))
      (node (ref "U5") (pin "4") (pinfunction "RSET_4") (pintype "passive"))
    )
    (net (code "44") (name "Net-(U5-SDO)") (class "Default")
      (node (ref "L10") (pin "1") (pinfunction "1_1") (pintype "passive"))
      (node (ref "R26") (pin "2") (pinfunction "2_2") (pintype "passive"))
      (node (ref "R7") (pin "1") (pinfunction "1_1") (pintype "passive"))
      (node (ref "U5") (pin "2") (pinfunction "SDO_2") (pintype "passive"))
    )
    (net (code "45") (name "Net-(U5-VCC)") (class "Default")
      (node (ref "C21") (pin "2") (pinfunction "2_2") (pintype "passive"))
      (node (ref "C36") (pin "2") (pinfunction "2_2") (pintype "passive"))
      (node (ref "L6") (pin "2") (pinfunction "2_2") (pintype "passive"))
      (node (ref "R22") (pin "1") (pinfunction "1_1") (pintype "passive"))
      (node (ref "R26") (pin "1") (pinfunction "1_1") (pintype "passive"))
      (node (ref "U5") (pin "8") (pinfunction "VCC_8") (pintype "power_in"))
    )
    (net (code "46") (name "Net-(U5-~{SDO})") (class "Default")
      (node (ref "R22") (pin "2") (pinfunction "2_2") (pintype "passive"))
      (node (ref "U5") (pin "1") (pinfunction "~{SDO}_1") (pintype "passive"))
    )
    (net (code "47") (name "Net-(U6-RSET)") (class "Default")
      (node (ref "R31") (pin "2") (pinfunction "2_2") (pintype "passive"))
      (node (ref "U6") (pin "4") (pinfunction "RSET_4") (pintype "passive"))
    )
    (net (code "48") (name "Net-(U6-SDO)") (class "Default")
      (node (ref "L11") (pin "1") (pinfunction "1_1") (pintype "passive"))
      (node (ref "R27") (pin "2") (pinfunction "2_2") (pintype "passive"))
      (node (ref "R8") (pin "1") (pinfunction "1_1") (pintype "passive"))
      (node (ref "U6") (pin "2") (pinfunction "SDO_2") (pintype "passive"))
    )
    (net (code "49") (name "Net-(U6-VCC)") (class "Default")
      (node (ref "C22") (pin "2") (pinfunction "2_2") (pintype "passive"))
      (node (ref "C37") (pin "2") (pinfunction "2_2") (pintype "passive"))
      (node (ref "L7") (pin "2") (pinfunction "2_2") (pintype "passive"))
      (node (ref "R23") (pin "1") (pinfunction "1_1") (pintype "passive"))
      (node (ref "R27") (pin "1") (pinfunction "1_1") (pintype "passive"))
      (node (ref "U6") (pin "8") (pinfunction "VCC_8") (pintype "power_in"))
    )
    (net (code "50") (name "Net-(U6-~{SDO})") (class "Default")
      (node (ref "R23") (pin "2") (pinfunction "2_2") (pintype "passive"))
      (node (ref "U6") (pin "1") (pinfunction "~{SDO}_1") (pintype "passive"))
    )
    (net (code "51") (name "Net-(U7-RSET)") (class "Default")
      (node (ref "R32") (pin "2") (pinfunction "2_2") (pintype "passive"))
      (node (ref "U7") (pin "4") (pinfunction "RSET_4") (pintype "passive"))
    )
    (net (code "52") (name "Net-(U7-SDO)") (class "Default")
      (node (ref "L12") (pin "1") (pinfunction "1_1") (pintype "passive"))
      (node (ref "R28") (pin "2") (pinfunction "2_2") (pintype "passive"))
      (node (ref "R9") (pin "1") (pinfunction "1_1") (pintype "passive"))
      (node (ref "U7") (pin "2") (pinfunction "SDO_2") (pintype "passive"))
    )
    (net (code "53") (name "Net-(U7-VCC)") (class "Default")
      (node (ref "C23") (pin "2") (pinfunction "2_2") (pintype "passive"))
      (node (ref "C38") (pin "2") (pinfunction "2_2") (pintype "passive"))
      (node (ref "L8") (pin "2") (pinfunction "2_2") (pintype "passive"))
      (node (ref "R24") (pin "1") (pinfunction "1_1") (pintype "passive"))
      (node (ref "R28") (pin "1") (pinfunction "1_1") (pintype "passive"))
      (node (ref "U7") (pin "8") (pinfunction "VCC_8") (pintype "power_in"))
    )
    (net (code "54") (name "Net-(U7-~{SDO})") (class "Default")
      (node (ref "R24") (pin "2") (pinfunction "2_2") (pintype "passive"))
      (node (ref "U7") (pin "1") (pinfunction "~{SDO}_1") (pintype "passive"))
    )
    (net (code "55") (name "REL") (class "Default")
      (node (ref "D2") (pin "1") (pinfunction "C_1") (pintype "passive"))
      (node (ref "RE1") (pin "7") (pinfunction "W+_7") (pintype "passive"))
      (node (ref "RE2") (pin "7") (pinfunction "W+_7") (pintype "passive"))
    )
    (net (code "56") (name "unconnected-(D2-K-Pad3)") (class "Default")
      (node (ref "D2") (pin "3") (pinfunction "K_3") (pintype "passive"))
    )
    (net (code "57") (name "unconnected-(U2-HIGH_Z-Pad13)") (class "Default")
      (node (ref "U2") (pin "13") (pinfunction "HIGH_Z_13") (pintype "passive"))
    )
    (net (code "58") (name "unconnected-(U2-OEM-Pad8)") (class "Default")
      (node (ref "U2") (pin "8") (pinfunction "OEM_8") (pintype "passive"))
    )
    (net (code "59") (name "unconnected-(U2-SSI{slash}~{CD}-Pad12)") (class "Default")
      (node (ref "U2") (pin "12") (pinfunction "SSI/~{CD}_12") (pintype "passive"))
    )
    (net (code "60") (name "unconnected-(U3-SCO-Pad23)") (class "Default")
      (node (ref "U3") (pin "23") (pinfunction "SCO_23") (pintype "passive"))
    )
    (net (code "61") (name "unconnected-(U3-~{SCO}-Pad22)") (class "Default")
      (node (ref "U3") (pin "22") (pinfunction "~{SCO}_22") (pintype "passive"))
    )
  )
)
